# Boost_Converter.net
KiCad netlist of a schematic drawn in Altium Designer
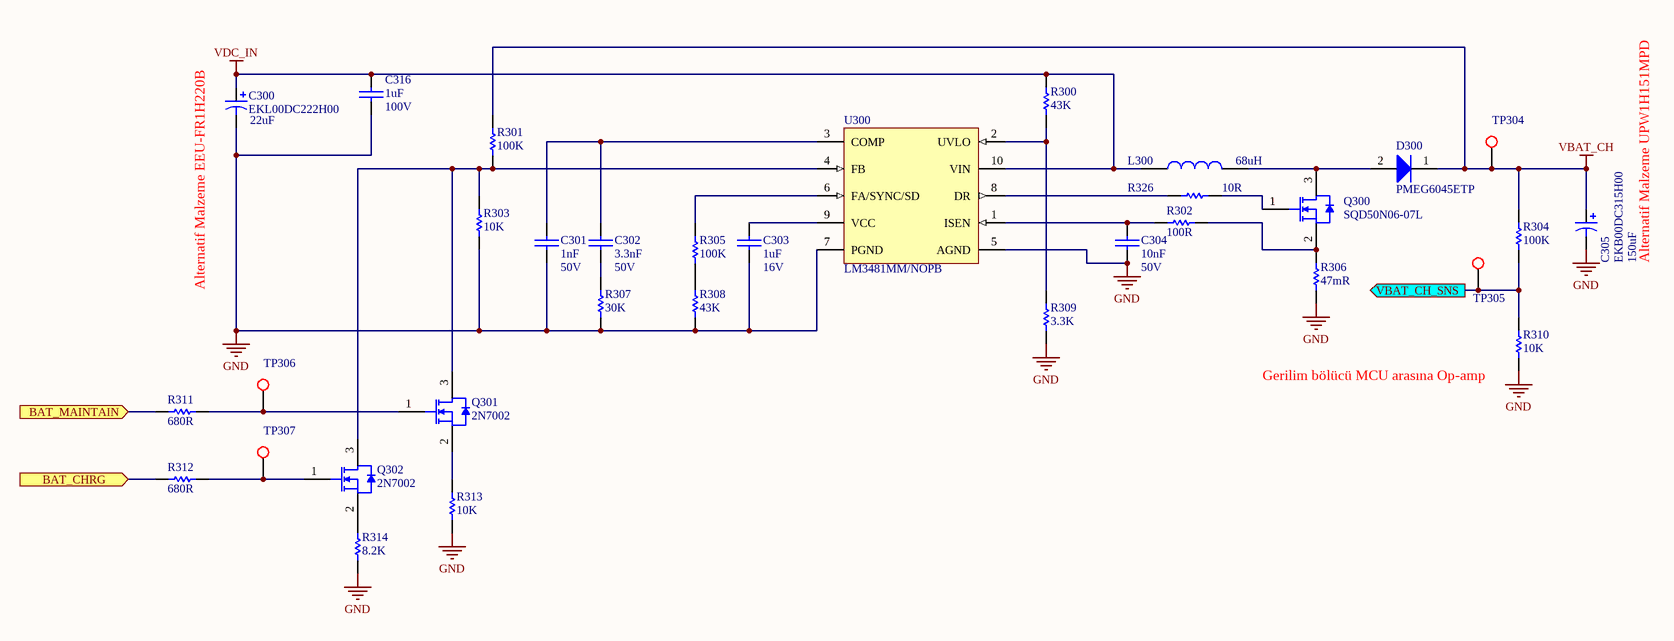
[diagram p0: Boost_Converter.SchDoc]

(export (version "E")
  (design (tool "Eeschema 10.0.6"))
  (components
    (comp (ref "C300")
      (value "EKL00DC222H00")
      (footprint "CAPPR5-10X12.5")
      (description "Aluminum Electrolytic Capacitor, Radial Style with Long Leads: 22uF, 50V")
      (fields (field (name "ALTIUM_VALUE") "22uF") (field (name "PUBLISHER") "Altium Limited"))
      (libsource (lib "Vishay Roederstein Electrolytic Radial-Lead Capacitor") (part "EKL00DC222H00"))
    )
    (comp (ref "C301")
      (value "1nF")
      (footprint "CAPC1005X06N")
      (description "CAP, CER, C0G, 1nF, %5, 50V, 0402")
      (fields
        (field (name "MANUFACTURER") "Murata")
        (field (name "MANUFACTURER PART NUMBER") "GRM1555C1H102JA01D")
        (field (name "OPERATING VOLTAGE") "50V")
      )
      (libsource (lib "Anime_Capacitor") (part "ACC0-0100-S272-0000"))
    )
    (comp (ref "C302")
      (value "3.3nF")
      (footprint "CAPC1005X06N")
      (description "CAP, CER, X7R, 3.3nF, %10, 50V, 0402")
      (fields
        (field (name "MANUFACTURER") "Murata")
        (field (name "MANUFACTURER PART NUMBER") "GRM155R71H332KA01D")
        (field (name "OPERATING VOLTAGE") "50V")
      )
      (libsource (lib "Anime_Capacitor") (part "ACC7-0330-S271-0000"))
    )
    (comp (ref "C303")
      (value "1uF")
      (footprint "CAPC2012X14N")
      (description "CAP, CER, X7R, 1uF, %10, 16V, 0805")
      (fields
        (field (name "MANUFACTURER") "Murata")
        (field (name "MANUFACTURER PART NUMBER") "GRM21BR71C105KA01L")
        (field (name "OPERATING VOLTAGE") "16V")
      )
      (libsource (lib "Anime_Capacitor") (part "ACC7-3100-S441-0000"))
    )
    (comp (ref "C304")
      (value "10nF")
      (footprint "CAPC1005X06N")
      (description "CAP, CER, X7R, 10nF, %10, 50V, 0402")
      (fields
        (field (name "MANUFACTURER") "Murata")
        (field (name "MANUFACTURER PART NUMBER") "GRM155R71H103KA88D")
        (field (name "OPERATING VOLTAGE") "50V")
      )
      (libsource (lib "Anime_Capacitor") (part "ACC7-1100-S271-0000"))
    )
    (comp (ref "C305")
      (value "EKB00DC315H00")
      (footprint "CAPPR5-10X12.5")
      (description "Aluminum Electrolytic Capacitor, Radial Style with Long Leads: 150uF, 50V")
      (fields (field (name "ALTIUM_VALUE") "150uF") (field (name "PUBLISHER") "Altium Limited"))
      (libsource (lib "Vishay Roederstein Electrolytic Radial-Lead Capacitor") (part "EKB00DC315H00"))
    )
    (comp (ref "C316")
      (value "1uF")
      (footprint "CAPC3216X09N")
      (description "CAP, CER, X7R, 1uF, %10, 100V, 1206")
      (fields
        (field (name "MANUFACTURER") "Murata")
        (field (name "MANUFACTURER PART NUMBER") "GRM31CR72A105KA01L")
        (field (name "OPERATING VOLTAGE") "100V")
      )
      (libsource (lib "Anime_Capacitor") (part "ACC7-3100-S691-0000"))
    )
    (comp (ref "D300")
      (value "PMEG6045ETP")
      (footprint "DIOM3825X11N")
      (description "Diode, Schottky, 0.53V @4.5A, 60V, SOD-128")
      (fields (field (name "MANUFACTURER") "NXP"))
      (libsource (lib "Anime_Semiconductor") (part "AS15-945M-SI10-0000"))
    )
    (comp (ref "L300")
      (value "68uH")
      (footprint "INDM120120X100N")
      (description "Inductor, Power, 68uH, 3A, 0.1ohm, SMD")
      (fields (field (name "MANUFACTURER") "Bourns") (field (name "MANUFACTURER PART NUMBER") "SRR1210-680M"))
      (libsource (lib "Anime_Inductor") (part "AL17-1680-SN35-3300"))
    )
    (comp (ref "Q300")
      (value "SQD50N06-07L")
      (footprint "TO228P970-3N")
      (description "Transistor, MOSFET, N, 60V, 50A, 7.6mR, SQD50N06-07L, TO-252")
      (fields
        (field (name "MANUFACTURER PART NUMBER") "SQD50N06-07L-GE3")
        (field (name "MANUFACTURER") "VISHAY")
      )
      (libsource (lib "Anime_Semiconductor") (part "AS26-A50M-SI40-0000"))
    )
    (comp (ref "Q301")
      (value "2N7002")
      (footprint "SOT90P247X115-3N")
      (description "Transistor, MOSFET, N, 60V, 115mA, 2N7002, SOT23")
      (fields (field (name "MANUFACTURER") "Fairchild"))
      (libsource (lib "Anime_Semiconductor") (part "AS26-810M-SI20-0000"))
    )
    (comp (ref "Q302")
      (value "2N7002")
      (footprint "SOT90P247X115-3N")
      (description "Transistor, MOSFET, N, 60V, 115mA, 2N7002, SOT23")
      (fields (field (name "MANUFACTURER") "Fairchild"))
      (libsource (lib "Anime_Semiconductor") (part "AS26-810M-SI20-0000"))
    )
    (comp (ref "R300")
      (value "43K")
      (footprint "RESC1005X04N")
      (description "RES, E24, Thick Film, SMD, 43K, 1%, 0.1W, 0402")
      (fields
        (field (name "MANUFACTURER") "Panasonic")
        (field (name "MANUFACTURER PART NUMBER") "ERJ-2RKF4302X")
      )
      (libsource (lib "Anime_Resistor") (part "AR19-4430-S2B2-0000"))
    )
    (comp (ref "R301")
      (value "100K")
      (footprint "RESC1005X04N")
      (description "RES, E24, Thick Film, SMD, 100K, 1%, 0.1W, 0402")
      (fields
        (field (name "MANUFACTURER") "Panasonic")
        (field (name "MANUFACTURER PART NUMBER") "ERJ-2RKF1003X")
      )
      (libsource (lib "Anime_Resistor") (part "AR19-5100-S2B2-0000"))
    )
    (comp (ref "R302")
      (value "100R")
      (footprint "RESC1005X04N")
      (description "RES, E24, Thick Film, SMD, 100R, 1%, 0.1W, 0402")
      (fields
        (field (name "MANUFACTURER") "Panasonic")
        (field (name "MANUFACTURER PART NUMBER") "ERJ-2RKF1000X")
      )
      (libsource (lib "Anime_Resistor") (part "AR19-2100-S2B2-0000"))
    )
    (comp (ref "R303")
      (value "10K")
      (footprint "RESC1005X04N")
      (description "RES, E24, Thick Film, SMD, 10K, 1%, 0.1W, 0402")
      (fields
        (field (name "MANUFACTURER") "Panasonic")
        (field (name "MANUFACTURER PART NUMBER") "ERJ-2RKF1002X")
      )
      (libsource (lib "Anime_Resistor") (part "AR19-4100-S2B2-0000"))
    )
    (comp (ref "R304")
      (value "100K")
      (footprint "RESC1005X04N")
      (description "RES, E24, Thick Film, SMD, 100K, 1%, 0.1W, 0402")
      (fields
        (field (name "MANUFACTURER") "Panasonic")
        (field (name "MANUFACTURER PART NUMBER") "ERJ-2RKF1003X")
      )
      (libsource (lib "Anime_Resistor") (part "AR19-5100-S2B2-0000"))
    )
    (comp (ref "R305")
      (value "100K")
      (footprint "RESC1005X04N")
      (description "RES, E24, Thick Film, SMD, 100K, 1%, 0.1W, 0402")
      (fields
        (field (name "MANUFACTURER") "Panasonic")
        (field (name "MANUFACTURER PART NUMBER") "ERJ-2RKF1003X")
      )
      (libsource (lib "Anime_Resistor") (part "AR19-5100-S2B2-0000"))
    )
    (comp (ref "R306")
      (value "47mR")
      (footprint "RESC3216X08N")
      (description "RES, Thick Film, SMD, 47mR, 1%, 1W, 1206")
      (fields
        (field (name "MANUFACTURER") "Panasonic")
        (field (name "MANUFACTURER PART NUMBER") "ERJ-8BWFR047V")
      )
      (libsource (lib "Anime_Resistor") (part "AR19-Y470-S5D2-0000"))
    )
    (comp (ref "R307")
      (value "30K")
      (footprint "RESC1005X04N")
      (description "RES, E24, Thick Film, SMD, 30K, 1%, 0.1W, 0402")
      (fields
        (field (name "MANUFACTURER") "Panasonic")
        (field (name "MANUFACTURER PART NUMBER") "ERJ-2RKF3002X")
      )
      (libsource (lib "Anime_Resistor") (part "AR19-4300-S2B2-0000"))
    )
    (comp (ref "R308")
      (value "43K")
      (footprint "RESC1005X04N")
      (description "RES, E24, Thick Film, SMD, 43K, 1%, 0.1W, 0402")
      (fields
        (field (name "MANUFACTURER") "Panasonic")
        (field (name "MANUFACTURER PART NUMBER") "ERJ-2RKF4302X")
      )
      (libsource (lib "Anime_Resistor") (part "AR19-4430-S2B2-0000"))
    )
    (comp (ref "R309")
      (value "3.3K")
      (footprint "RESC1005X04N")
      (description "RES, E24, Thick Film, SMD, 3.3K, 1%, 0.1W, 0402")
      (fields
        (field (name "MANUFACTURER") "Panasonic")
        (field (name "MANUFACTURER PART NUMBER") "ERJ-2RKF3301X")
      )
      (libsource (lib "Anime_Resistor") (part "AR19-3330-S2B2-0000"))
    )
    (comp (ref "R310")
      (value "10K")
      (footprint "RESC1005X04N")
      (description "RES, E24, Thick Film, SMD, 10K, 1%, 0.1W, 0402")
      (fields
        (field (name "MANUFACTURER") "Panasonic")
        (field (name "MANUFACTURER PART NUMBER") "ERJ-2RKF1002X")
      )
      (libsource (lib "Anime_Resistor") (part "AR19-4100-S2B2-0000"))
    )
    (comp (ref "R311")
      (value "680R")
      (footprint "RESC1005X04N")
      (description "RES, E24, Thick Film, SMD, 680R, 1%, 0.1W, 0402")
      (fields
        (field (name "MANUFACTURER") "Panasonic")
        (field (name "MANUFACTURER PART NUMBER") "ERJ-2RKF6800X")
      )
      (libsource (lib "Anime_Resistor") (part "AR19-2680-S2B2-0000"))
    )
    (comp (ref "R312")
      (value "680R")
      (footprint "RESC1005X04N")
      (description "RES, E24, Thick Film, SMD, 680R, 1%, 0.1W, 0402")
      (fields
        (field (name "MANUFACTURER") "Panasonic")
        (field (name "MANUFACTURER PART NUMBER") "ERJ-2RKF6800X")
      )
      (libsource (lib "Anime_Resistor") (part "AR19-2680-S2B2-0000"))
    )
    (comp (ref "R313")
      (value "10K")
      (footprint "RESC1005X04N")
      (description "RES, E24, Thick Film, SMD, 10K, 1%, 0.1W, 0402")
      (fields
        (field (name "MANUFACTURER") "Panasonic")
        (field (name "MANUFACTURER PART NUMBER") "ERJ-2RKF1002X")
      )
      (libsource (lib "Anime_Resistor") (part "AR19-4100-S2B2-0000"))
    )
    (comp (ref "R314")
      (value "8.2K")
      (footprint "RESC1005X04N")
      (description "RES, E24, Thick Film, SMD, 8.2K, 1%, 0.1W, 0402")
      (fields
        (field (name "MANUFACTURER") "Panasonic")
        (field (name "MANUFACTURER PART NUMBER") "ERJ-2RKF8201X")
      )
      (libsource (lib "Anime_Resistor") (part "AR19-3820-S2B2-0000"))
    )
    (comp (ref "R326")
      (value "10R")
      (footprint "RESC1005X04N")
      (description "RES, E24, Thick Film, SMD, 10R, 1%, 0.1W, 0402")
      (fields
        (field (name "MANUFACTURER") "Panasonic")
        (field (name "MANUFACTURER PART NUMBER") "ERJ-2RKF10R0X")
      )
      (libsource (lib "Anime_Resistor") (part "AR19-1100-S2B2-0000"))
    )
    (comp (ref "TP304")
      (value "AEMT-C00S-1000-0000")
      (footprint "TP100")
      (description "Test Point, Circular, 1mm")
      (libsource (lib "Anime_Electromechanical") (part "AEMT-C00S-1000-0000"))
    )
    (comp (ref "TP305")
      (value "AEMT-C00S-1000-0000")
      (footprint "TP100")
      (description "Test Point, Circular, 1mm")
      (libsource (lib "Anime_Electromechanical") (part "AEMT-C00S-1000-0000"))
    )
    (comp (ref "TP306")
      (value "AEMT-C00S-1000-0000")
      (footprint "TP100")
      (description "Test Point, Circular, 1mm")
      (libsource (lib "Anime_Electromechanical") (part "AEMT-C00S-1000-0000"))
    )
    (comp (ref "TP307")
      (value "AEMT-C00S-1000-0000")
      (footprint "TP100")
      (description "Test Point, Circular, 1mm")
      (libsource (lib "Anime_Electromechanical") (part "AEMT-C00S-1000-0000"))
    )
    (comp (ref "U300")
      (value "LM3481MM/NOPB")
      (footprint "MUB10A_N")
      (description "High Efficiency Low-Side N-Channel Controller for Switching Regulators, 10-pin MSOP, Pb-Free")
      (fields (field (name "MANUFACTURER") "National Semiconductor"))
      (libsource (lib "National Semiconductor MiscPower") (part "LM3481MM/NOPB"))
    )
  )
  (nets
    (net (code "1") (name "/BAT_CHRG") (class "Default")
      (node (ref "R312") (pin "2") (pinfunction "2_2") (pintype "passive"))
    )
    (net (code "2") (name "/BAT_MAINTAIN") (class "Default")
      (node (ref "R311") (pin "2") (pinfunction "2_2") (pintype "passive"))
    )
    (net (code "3") (name "/VBAT_CH_SNS") (class "Default")
      (node (ref "R304") (pin "1") (pinfunction "1_1") (pintype "passive"))
      (node (ref "R310") (pin "2") (pinfunction "2_2") (pintype "passive"))
      (node (ref "TP305") (pin "1") (pintype "passive"))
    )
    (net (code "4") (name "GND") (class "Default")
      (node (ref "C300") (pin "2") (pinfunction "2_2") (pintype "passive"))
      (node (ref "C301") (pin "1") (pintype "passive"))
      (node (ref "C303") (pin "1") (pintype "passive"))
      (node (ref "C304") (pin "1") (pintype "passive"))
      (node (ref "C305") (pin "2") (pinfunction "2_2") (pintype "passive"))
      (node (ref "C316") (pin "1") (pintype "passive"))
      (node (ref "R303") (pin "1") (pinfunction "1_1") (pintype "passive"))
      (node (ref "R306") (pin "2") (pinfunction "2_2") (pintype "passive"))
      (node (ref "R307") (pin "1") (pinfunction "1_1") (pintype "passive"))
      (node (ref "R308") (pin "1") (pinfunction "1_1") (pintype "passive"))
      (node (ref "R309") (pin "1") (pinfunction "1_1") (pintype "passive"))
      (node (ref "R310") (pin "1") (pinfunction "1_1") (pintype "passive"))
      (node (ref "R313") (pin "1") (pinfunction "1_1") (pintype "passive"))
      (node (ref "R314") (pin "1") (pinfunction "1_1") (pintype "passive"))
      (node (ref "U300") (pin "5") (pinfunction "AGND_5") (pintype "power_in"))
      (node (ref "U300") (pin "7") (pinfunction "PGND_7") (pintype "power_in"))
    )
    (net (code "5") (name "Net-(C302-Pad1)") (class "Default")
      (node (ref "C302") (pin "1") (pintype "passive"))
      (node (ref "R307") (pin "2") (pinfunction "2_2") (pintype "passive"))
    )
    (net (code "6") (name "Net-(D300-A)") (class "Default")
      (node (ref "D300") (pin "2") (pinfunction "A_2") (pintype "passive"))
      (node (ref "L300") (pin "2") (pinfunction "2_2") (pintype "passive"))
      (node (ref "Q300") (pin "3") (pinfunction "Drain_3") (pintype "passive"))
    )
    (net (code "7") (name "Net-(Q300-Gate)") (class "Default")
      (node (ref "Q300") (pin "1") (pinfunction "Gate_1") (pintype "passive"))
      (node (ref "R326") (pin "2") (pinfunction "2_2") (pintype "passive"))
    )
    (net (code "8") (name "Net-(Q300-Source)") (class "Default")
      (node (ref "Q300") (pin "2") (pinfunction "Source_2") (pintype "passive"))
      (node (ref "R302") (pin "2") (pinfunction "2_2") (pintype "passive"))
      (node (ref "R306") (pin "1") (pinfunction "1_1") (pintype "passive"))
    )
    (net (code "9") (name "Net-(Q301-Drain)") (class "Default")
      (node (ref "Q301") (pin "3") (pinfunction "Drain_3") (pintype "passive"))
      (node (ref "Q302") (pin "3") (pinfunction "Drain_3") (pintype "passive"))
      (node (ref "R301") (pin "1") (pinfunction "1_1") (pintype "passive"))
      (node (ref "R303") (pin "2") (pinfunction "2_2") (pintype "passive"))
      (node (ref "U300") (pin "4") (pinfunction "FB_4") (pintype "input"))
    )
    (net (code "10") (name "Net-(Q301-Gate)") (class "Default")
      (node (ref "Q301") (pin "1") (pinfunction "Gate_1") (pintype "passive"))
      (node (ref "R311") (pin "1") (pinfunction "1_1") (pintype "passive"))
      (node (ref "TP306") (pin "1") (pintype "passive"))
    )
    (net (code "11") (name "Net-(Q301-Source)") (class "Default")
      (node (ref "Q301") (pin "2") (pinfunction "Source_2") (pintype "passive"))
      (node (ref "R313") (pin "2") (pinfunction "2_2") (pintype "passive"))
    )
    (net (code "12") (name "Net-(Q302-Gate)") (class "Default")
      (node (ref "Q302") (pin "1") (pinfunction "Gate_1") (pintype "passive"))
      (node (ref "R312") (pin "1") (pinfunction "1_1") (pintype "passive"))
      (node (ref "TP307") (pin "1") (pintype "passive"))
    )
    (net (code "13") (name "Net-(Q302-Source)") (class "Default")
      (node (ref "Q302") (pin "2") (pinfunction "Source_2") (pintype "passive"))
      (node (ref "R314") (pin "2") (pinfunction "2_2") (pintype "passive"))
    )
    (net (code "14") (name "Net-(R305-Pad1)") (class "Default")
      (node (ref "R305") (pin "1") (pinfunction "1_1") (pintype "passive"))
      (node (ref "R308") (pin "2") (pinfunction "2_2") (pintype "passive"))
    )
    (net (code "15") (name "Net-(U300-COMP)") (class "Default")
      (node (ref "C301") (pin "2") (pintype "passive"))
      (node (ref "C302") (pin "2") (pintype "passive"))
      (node (ref "U300") (pin "3") (pinfunction "COMP_3") (pintype "passive"))
    )
    (net (code "16") (name "Net-(U300-DR)") (class "Default")
      (node (ref "R326") (pin "1") (pinfunction "1_1") (pintype "passive"))
      (node (ref "U300") (pin "8") (pinfunction "DR_8") (pintype "output"))
    )
    (net (code "17") (name "Net-(U300-FA{slash}SYNC{slash}SD)") (class "Default")
      (node (ref "R305") (pin "2") (pinfunction "2_2") (pintype "passive"))
      (node (ref "U300") (pin "6") (pinfunction "FA/SYNC/SD_6") (pintype "input"))
    )
    (net (code "18") (name "Net-(U300-ISEN)") (class "Default")
      (node (ref "C304") (pin "2") (pintype "passive"))
      (node (ref "R302") (pin "1") (pinfunction "1_1") (pintype "passive"))
      (node (ref "U300") (pin "1") (pinfunction "ISEN_1") (pintype "input"))
    )
    (net (code "19") (name "Net-(U300-UVLO)") (class "Default")
      (node (ref "R300") (pin "1") (pinfunction "1_1") (pintype "passive"))
      (node (ref "R309") (pin "2") (pinfunction "2_2") (pintype "passive"))
      (node (ref "U300") (pin "2") (pinfunction "UVLO_2") (pintype "input"))
    )
    (net (code "20") (name "Net-(U300-VCC)") (class "Default")
      (node (ref "C303") (pin "2") (pintype "passive"))
      (node (ref "U300") (pin "9") (pinfunction "VCC_9") (pintype "power_in"))
    )
    (net (code "21") (name "VBAT_CH") (class "Default")
      (node (ref "C305") (pin "1") (pinfunction "1_1") (pintype "passive"))
      (node (ref "D300") (pin "1") (pinfunction "K_1") (pintype "passive"))
      (node (ref "R301") (pin "2") (pinfunction "2_2") (pintype "passive"))
      (node (ref "R304") (pin "2") (pinfunction "2_2") (pintype "passive"))
      (node (ref "TP304") (pin "1") (pintype "passive"))
    )
    (net (code "22") (name "VDC_IN") (class "Default")
      (node (ref "C300") (pin "1") (pinfunction "1_1") (pintype "passive"))
      (node (ref "C316") (pin "2") (pintype "passive"))
      (node (ref "L300") (pin "1") (pinfunction "1_1") (pintype "passive"))
      (node (ref "R300") (pin "2") (pinfunction "2_2") (pintype "passive"))
      (node (ref "U300") (pin "10") (pinfunction "VIN_10") (pintype "power_in"))
    )
  )
)
